# PCB.net
KiCad netlist of a schematic drawn in EasyEDA Pro
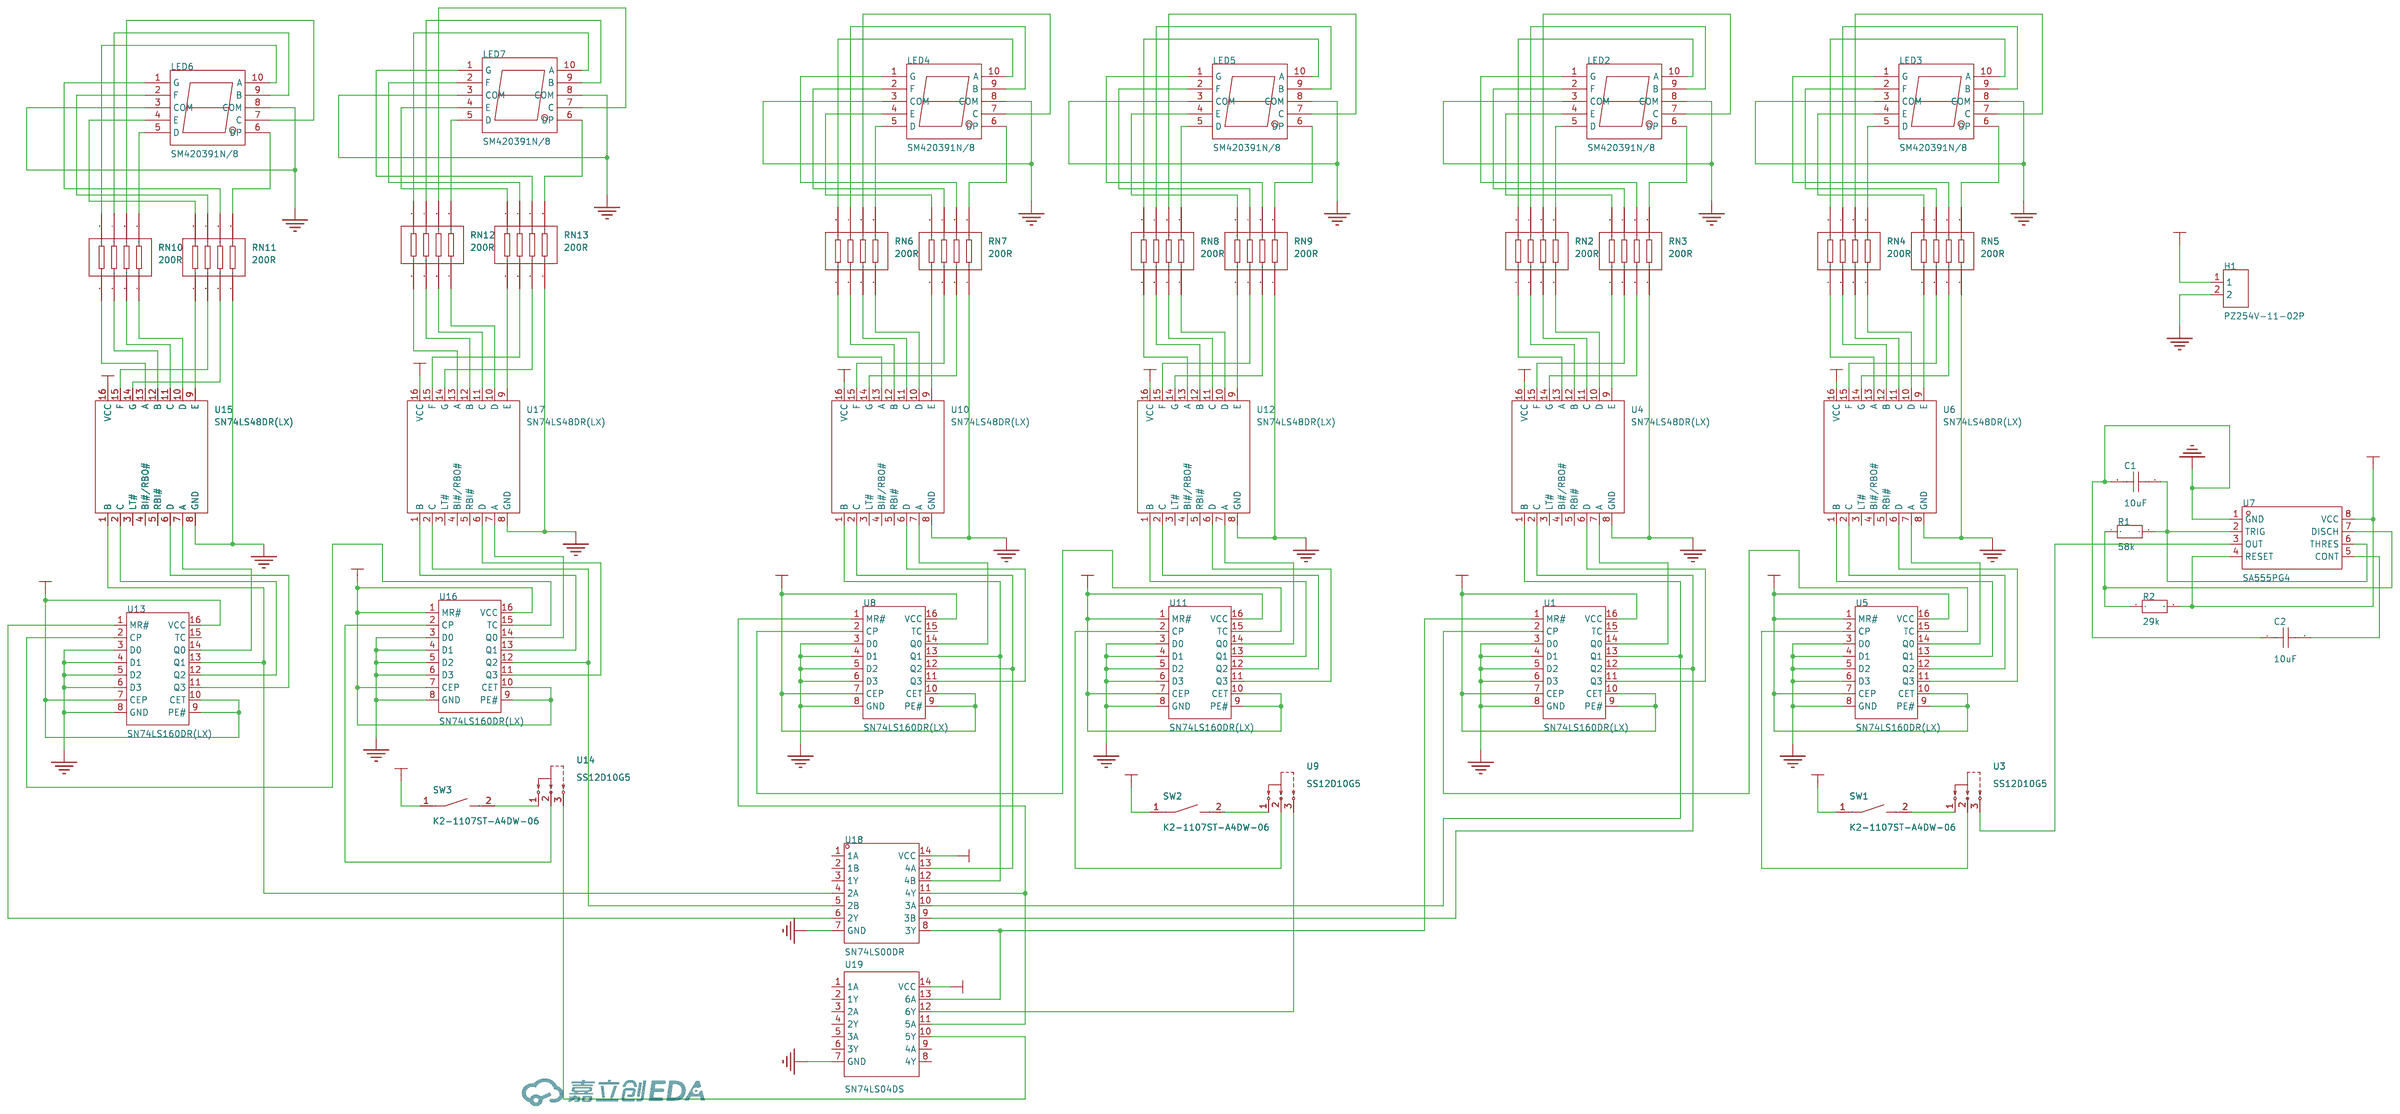
[diagram p0: schematic sheet]

(export (version "E")
  (design (tool "Eeschema 10.0.6"))
  (components
    (comp (ref "C1")
      (value "10uF")
      (footprint "easyedapro:C0603")
      (description "容值:100nF;精度:±10%;额定电压:50V;温度系数:X7R;")
      (fields
        (field (name "Manufacturer Part") "CGA0603X7R104K500JT")
        (field (name "Manufacturer") "HRE(芯声)")
      )
      (libsource (lib "easyedapro") (part "CGA0603X7R104K500JT"))
    )
    (comp (ref "C2")
      (value "10uF")
      (footprint "easyedapro:C0603")
      (description "容值:100nF;精度:±10%;额定电压:50V;温度系数:X7R;")
      (fields
        (field (name "Manufacturer Part") "CGA0603X7R104K500JT")
        (field (name "Manufacturer") "HRE(芯声)")
      )
      (libsource (lib "easyedapro") (part "CGA0603X7R104K500JT"))
    )
    (comp (ref "H1")
      (value "PZ254V-11-02P")
      (footprint "easyedapro:HDR-TH_2P-P2.54-V-M")
      (fields (field (name "Manufacturer") "XFCN(兴飞)"))
      (libsource (lib "easyedapro") (part "PZ254V-11-02P"))
    )
    (comp (ref "LED2")
      (value "SM420391N/8")
      (footprint "easyedapro:LED-SEG-TH_10P-L10.0-W13.0-P2.54-S7.62-TL")
      (description "数码管位数:1位;字符尺寸(英寸):0.39;发光颜色:红色;LED极性:共阴极;")
      (fields (field (name "Manufacturer") "ARKLED(方舟)"))
      (libsource (lib "easyedapro") (part "SM420391N/8"))
    )
    (comp (ref "LED3")
      (value "SM420391N/8")
      (footprint "easyedapro:LED-SEG-TH_10P-L10.0-W13.0-P2.54-S7.62-TL")
      (description "数码管位数:1位;字符尺寸(英寸):0.39;发光颜色:红色;LED极性:共阴极;")
      (fields (field (name "Manufacturer") "ARKLED(方舟)"))
      (libsource (lib "easyedapro") (part "SM420391N/8"))
    )
    (comp (ref "LED4")
      (value "SM420391N/8")
      (footprint "easyedapro:LED-SEG-TH_10P-L10.0-W13.0-P2.54-S7.62-TL")
      (description "数码管位数:1位;字符尺寸(英寸):0.39;发光颜色:红色;LED极性:共阴极;")
      (fields (field (name "Manufacturer") "ARKLED(方舟)"))
      (libsource (lib "easyedapro") (part "SM420391N/8"))
    )
    (comp (ref "LED5")
      (value "SM420391N/8")
      (footprint "easyedapro:LED-SEG-TH_10P-L10.0-W13.0-P2.54-S7.62-TL")
      (description "数码管位数:1位;字符尺寸(英寸):0.39;发光颜色:红色;LED极性:共阴极;")
      (fields (field (name "Manufacturer") "ARKLED(方舟)"))
      (libsource (lib "easyedapro") (part "SM420391N/8"))
    )
    (comp (ref "LED6")
      (value "SM420391N/8")
      (footprint "easyedapro:LED-SEG-TH_10P-L10.0-W13.0-P2.54-S7.62-TL")
      (description "数码管位数:1位;字符尺寸(英寸):0.39;发光颜色:红色;LED极性:共阴极;")
      (fields (field (name "Manufacturer") "ARKLED(方舟)"))
      (libsource (lib "easyedapro") (part "SM420391N/8"))
    )
    (comp (ref "LED7")
      (value "SM420391N/8")
      (footprint "easyedapro:LED-SEG-TH_10P-L10.0-W13.0-P2.54-S7.62-TL")
      (description "数码管位数:1位;字符尺寸(英寸):0.39;发光颜色:红色;LED极性:共阴极;")
      (fields (field (name "Manufacturer") "ARKLED(方舟)"))
      (libsource (lib "easyedapro") (part "SM420391N/8"))
    )
    (comp (ref "R1")
      (value "58k")
      (footprint "easyedapro:R2512")
      (description "电阻类型:采样电阻；合金电阻;阻值:5mΩ;精度:±1%;功率:3W;温度系数:±50ppm/°C;")
      (fields (field (name "Manufacturer Part") "JER2512F3R005") (field (name "Manufacturer") "JIERR(捷而瑞)"))
      (libsource (lib "easyedapro") (part "JER2512F3R005"))
    )
    (comp (ref "R2")
      (value "29k")
      (footprint "easyedapro:R2512")
      (description "电阻类型:采样电阻；合金电阻;阻值:5mΩ;精度:±1%;功率:3W;温度系数:±50ppm/°C;")
      (fields (field (name "Manufacturer Part") "JER2512F3R005") (field (name "Manufacturer") "JIERR(捷而瑞)"))
      (libsource (lib "easyedapro") (part "JER2512F3R005"))
    )
    (comp (ref "RN2")
      (value "200R")
      (footprint "easyedapro:RES-ARRAY-SMD_0603-8P-L3.2-W1.6-BL")
      (description "电阻器数:4;阻值:10kΩ;精度:±5%;单个元件功率:62.5mW;温度系数:±200ppm/°C;")
      (fields
        (field (name "Manufacturer Part") "4D03WGJ0103T5E")
        (field (name "Manufacturer") "UNI-ROYAL(厚声)")
      )
      (libsource (lib "easyedapro") (part "4D03WGJ0103T5E"))
    )
    (comp (ref "RN3")
      (value "200R")
      (footprint "easyedapro:RES-ARRAY-SMD_0603-8P-L3.2-W1.6-BL")
      (description "电阻器数:4;阻值:10kΩ;精度:±5%;单个元件功率:62.5mW;温度系数:±200ppm/°C;")
      (fields
        (field (name "Manufacturer Part") "4D03WGJ0103T5E")
        (field (name "Manufacturer") "UNI-ROYAL(厚声)")
      )
      (libsource (lib "easyedapro") (part "4D03WGJ0103T5E"))
    )
    (comp (ref "RN4")
      (value "200R")
      (footprint "easyedapro:RES-ARRAY-SMD_0603-8P-L3.2-W1.6-BL")
      (description "电阻器数:4;阻值:10kΩ;精度:±5%;单个元件功率:62.5mW;温度系数:±200ppm/°C;")
      (fields
        (field (name "Manufacturer Part") "4D03WGJ0103T5E")
        (field (name "Manufacturer") "UNI-ROYAL(厚声)")
      )
      (libsource (lib "easyedapro") (part "4D03WGJ0103T5E"))
    )
    (comp (ref "RN5")
      (value "200R")
      (footprint "easyedapro:RES-ARRAY-SMD_0603-8P-L3.2-W1.6-BL")
      (description "电阻器数:4;阻值:10kΩ;精度:±5%;单个元件功率:62.5mW;温度系数:±200ppm/°C;")
      (fields
        (field (name "Manufacturer Part") "4D03WGJ0103T5E")
        (field (name "Manufacturer") "UNI-ROYAL(厚声)")
      )
      (libsource (lib "easyedapro") (part "4D03WGJ0103T5E"))
    )
    (comp (ref "RN6")
      (value "200R")
      (footprint "easyedapro:RES-ARRAY-SMD_0603-8P-L3.2-W1.6-BL")
      (description "电阻器数:4;阻值:10kΩ;精度:±5%;单个元件功率:62.5mW;温度系数:±200ppm/°C;")
      (fields
        (field (name "Manufacturer Part") "4D03WGJ0103T5E")
        (field (name "Manufacturer") "UNI-ROYAL(厚声)")
      )
      (libsource (lib "easyedapro") (part "4D03WGJ0103T5E"))
    )
    (comp (ref "RN7")
      (value "200R")
      (footprint "easyedapro:RES-ARRAY-SMD_0603-8P-L3.2-W1.6-BL")
      (description "电阻器数:4;阻值:10kΩ;精度:±5%;单个元件功率:62.5mW;温度系数:±200ppm/°C;")
      (fields
        (field (name "Manufacturer Part") "4D03WGJ0103T5E")
        (field (name "Manufacturer") "UNI-ROYAL(厚声)")
      )
      (libsource (lib "easyedapro") (part "4D03WGJ0103T5E"))
    )
    (comp (ref "RN8")
      (value "200R")
      (footprint "easyedapro:RES-ARRAY-SMD_0603-8P-L3.2-W1.6-BL")
      (description "电阻器数:4;阻值:10kΩ;精度:±5%;单个元件功率:62.5mW;温度系数:±200ppm/°C;")
      (fields
        (field (name "Manufacturer Part") "4D03WGJ0103T5E")
        (field (name "Manufacturer") "UNI-ROYAL(厚声)")
      )
      (libsource (lib "easyedapro") (part "4D03WGJ0103T5E"))
    )
    (comp (ref "RN9")
      (value "200R")
      (footprint "easyedapro:RES-ARRAY-SMD_0603-8P-L3.2-W1.6-BL")
      (description "电阻器数:4;阻值:10kΩ;精度:±5%;单个元件功率:62.5mW;温度系数:±200ppm/°C;")
      (fields
        (field (name "Manufacturer Part") "4D03WGJ0103T5E")
        (field (name "Manufacturer") "UNI-ROYAL(厚声)")
      )
      (libsource (lib "easyedapro") (part "4D03WGJ0103T5E"))
    )
    (comp (ref "RN10")
      (value "200R")
      (footprint "easyedapro:RES-ARRAY-SMD_0603-8P-L3.2-W1.6-BL")
      (description "电阻器数:4;阻值:10kΩ;精度:±5%;单个元件功率:62.5mW;温度系数:±200ppm/°C;")
      (fields
        (field (name "Manufacturer Part") "4D03WGJ0103T5E")
        (field (name "Manufacturer") "UNI-ROYAL(厚声)")
      )
      (libsource (lib "easyedapro") (part "4D03WGJ0103T5E"))
    )
    (comp (ref "RN11")
      (value "200R")
      (footprint "easyedapro:RES-ARRAY-SMD_0603-8P-L3.2-W1.6-BL")
      (description "电阻器数:4;阻值:10kΩ;精度:±5%;单个元件功率:62.5mW;温度系数:±200ppm/°C;")
      (fields
        (field (name "Manufacturer Part") "4D03WGJ0103T5E")
        (field (name "Manufacturer") "UNI-ROYAL(厚声)")
      )
      (libsource (lib "easyedapro") (part "4D03WGJ0103T5E"))
    )
    (comp (ref "RN12")
      (value "200R")
      (footprint "easyedapro:RES-ARRAY-SMD_0603-8P-L3.2-W1.6-BL")
      (description "电阻器数:4;阻值:10kΩ;精度:±5%;单个元件功率:62.5mW;温度系数:±200ppm/°C;")
      (fields
        (field (name "Manufacturer Part") "4D03WGJ0103T5E")
        (field (name "Manufacturer") "UNI-ROYAL(厚声)")
      )
      (libsource (lib "easyedapro") (part "4D03WGJ0103T5E"))
    )
    (comp (ref "RN13")
      (value "200R")
      (footprint "easyedapro:RES-ARRAY-SMD_0603-8P-L3.2-W1.6-BL")
      (description "电阻器数:4;阻值:10kΩ;精度:±5%;单个元件功率:62.5mW;温度系数:±200ppm/°C;")
      (fields
        (field (name "Manufacturer Part") "4D03WGJ0103T5E")
        (field (name "Manufacturer") "UNI-ROYAL(厚声)")
      )
      (libsource (lib "easyedapro") (part "4D03WGJ0103T5E"))
    )
    (comp (ref "SW1")
      (value "K2-1107ST-A4DW-06")
      (footprint "easyedapro:KEY-SMD_L6.2-W3.6-LS8.0_K2-1107ST-A4SW-06")
      (fields (field (name "Manufacturer") "韩国韩荣"))
      (libsource (lib "easyedapro") (part "K2-1107ST-A4SW-06"))
    )
    (comp (ref "SW2")
      (value "K2-1107ST-A4DW-06")
      (footprint "easyedapro:KEY-SMD_L6.2-W3.6-LS8.0_K2-1107ST-A4SW-06")
      (fields (field (name "Manufacturer") "韩国韩荣"))
      (libsource (lib "easyedapro") (part "K2-1107ST-A4SW-06"))
    )
    (comp (ref "SW3")
      (value "K2-1107ST-A4DW-06")
      (footprint "easyedapro:KEY-SMD_L6.2-W3.6-LS8.0_K2-1107ST-A4SW-06")
      (fields (field (name "Manufacturer") "韩国韩荣"))
      (libsource (lib "easyedapro") (part "K2-1107ST-A4SW-06"))
    )
    (comp (ref "U1")
      (value "SN74LS160DR(LX)")
      (footprint "easyedapro:DIP-16_L19.4-W6.4-P2.54-S7.6-BL")
      (description "工作电压:2V~6V;触发沿:上升沿;计数速率:35MHz;")
      (fields (field (name "Manufacturer") "LX(灵星芯微)"))
      (libsource (lib "easyedapro") (part "SN74LS160N(LX)"))
    )
    (comp (ref "U3")
      (value "SS12D10G5")
      (footprint "easyedapro:SW-TH_SHOU-HAN_SS12D10G4")
      (description "电路结构:单刀双掷;安装方式:直插;额定电流:2A;额定电压:125V;工作寿命:3千次;")
      (fields (field (name "Manufacturer") "SHOU HAN(首韩)"))
      (libsource (lib "easyedapro") (part "SS12D10G5"))
    )
    (comp (ref "U4")
      (value "SN74LS48DR(LX)")
      (footprint "easyedapro:DIP-16_L19.2-W6.6-P2.54-LS8.8-BL")
      (description "接口类型:-;工作电压:2V~6V;时钟频率(fc):-;位驱动电流:-;段驱动电流:-;")
      (fields (field (name "Manufacturer") "LX(灵星芯微)"))
      (libsource (lib "easyedapro") (part "SN74LS48N(XBLW)"))
    )
    (comp (ref "U5")
      (value "SN74LS160DR(LX)")
      (footprint "easyedapro:DIP-16_L19.4-W6.4-P2.54-S7.6-BL")
      (description "工作电压:2V~6V;触发沿:上升沿;计数速率:35MHz;")
      (fields (field (name "Manufacturer") "LX(灵星芯微)"))
      (libsource (lib "easyedapro") (part "SN74LS160N(LX)"))
    )
    (comp (ref "U6")
      (value "SN74LS48DR(LX)")
      (footprint "easyedapro:DIP-16_L19.2-W6.6-P2.54-LS8.8-BL")
      (description "接口类型:-;工作电压:2V~6V;时钟频率(fc):-;位驱动电流:-;段驱动电流:-;")
      (fields (field (name "Manufacturer") "LX(灵星芯微)"))
      (libsource (lib "easyedapro") (part "SN74LS48N(XBLW)"))
    )
    (comp (ref "U7")
      (value "SA555PG4")
      (footprint "easyedapro:PDIP-8_L9.6-W6.4-P2.54-LS7.6-BL")
      (fields (field (name "Manufacturer") "TI(德州仪器)"))
      (libsource (lib "easyedapro") (part "SA555PG4"))
    )
    (comp (ref "U8")
      (value "SN74LS160DR(LX)")
      (footprint "easyedapro:DIP-16_L19.4-W6.4-P2.54-S7.6-BL")
      (description "工作电压:2V~6V;触发沿:上升沿;计数速率:35MHz;")
      (fields (field (name "Manufacturer") "LX(灵星芯微)"))
      (libsource (lib "easyedapro") (part "SN74LS160N(LX)"))
    )
    (comp (ref "U9")
      (value "SS12D10G5")
      (footprint "easyedapro:SW-TH_SHOU-HAN_SS12D10G4")
      (description "电路结构:单刀双掷;安装方式:直插;额定电流:2A;额定电压:125V;工作寿命:3千次;")
      (fields (field (name "Manufacturer") "SHOU HAN(首韩)"))
      (libsource (lib "easyedapro") (part "SS12D10G5"))
    )
    (comp (ref "U10")
      (value "SN74LS48DR(LX)")
      (footprint "easyedapro:DIP-16_L19.2-W6.6-P2.54-LS8.8-BL")
      (description "接口类型:-;工作电压:2V~6V;时钟频率(fc):-;位驱动电流:-;段驱动电流:-;")
      (fields (field (name "Manufacturer") "LX(灵星芯微)"))
      (libsource (lib "easyedapro") (part "SN74LS48N(XBLW)"))
    )
    (comp (ref "U11")
      (value "SN74LS160DR(LX)")
      (footprint "easyedapro:DIP-16_L19.4-W6.4-P2.54-S7.6-BL")
      (description "工作电压:2V~6V;触发沿:上升沿;计数速率:35MHz;")
      (fields (field (name "Manufacturer") "LX(灵星芯微)"))
      (libsource (lib "easyedapro") (part "SN74LS160N(LX)"))
    )
    (comp (ref "U12")
      (value "SN74LS48DR(LX)")
      (footprint "easyedapro:DIP-16_L19.2-W6.6-P2.54-LS8.8-BL")
      (description "接口类型:-;工作电压:2V~6V;时钟频率(fc):-;位驱动电流:-;段驱动电流:-;")
      (fields (field (name "Manufacturer") "LX(灵星芯微)"))
      (libsource (lib "easyedapro") (part "SN74LS48N(XBLW)"))
    )
    (comp (ref "U13")
      (value "SN74LS160DR(LX)")
      (footprint "easyedapro:DIP-16_L19.4-W6.4-P2.54-S7.6-BL")
      (description "工作电压:2V~6V;触发沿:上升沿;计数速率:35MHz;")
      (fields (field (name "Manufacturer") "LX(灵星芯微)"))
      (libsource (lib "easyedapro") (part "SN74LS160N(LX)"))
    )
    (comp (ref "U14")
      (value "SS12D10G5")
      (footprint "easyedapro:SW-TH_SHOU-HAN_SS12D10G4")
      (description "电路结构:单刀双掷;安装方式:直插;额定电流:2A;额定电压:125V;工作寿命:3千次;")
      (fields (field (name "Manufacturer") "SHOU HAN(首韩)"))
      (libsource (lib "easyedapro") (part "SS12D10G5"))
    )
    (comp (ref "U15")
      (value "SN74LS48DR(LX)")
      (footprint "easyedapro:DIP-16_L19.2-W6.6-P2.54-LS8.8-BL")
      (description "接口类型:-;工作电压:2V~6V;时钟频率(fc):-;位驱动电流:-;段驱动电流:-;")
      (fields (field (name "Manufacturer") "LX(灵星芯微)"))
      (libsource (lib "easyedapro") (part "SN74LS48N(XBLW)"))
    )
    (comp (ref "U16")
      (value "SN74LS160DR(LX)")
      (footprint "easyedapro:DIP-16_L19.4-W6.4-P2.54-S7.6-BL")
      (description "工作电压:2V~6V;触发沿:上升沿;计数速率:35MHz;")
      (fields (field (name "Manufacturer") "LX(灵星芯微)"))
      (libsource (lib "easyedapro") (part "SN74LS160N(LX)"))
    )
    (comp (ref "U17")
      (value "SN74LS48DR(LX)")
      (footprint "easyedapro:DIP-16_L19.2-W6.6-P2.54-LS8.8-BL")
      (description "接口类型:-;工作电压:2V~6V;时钟频率(fc):-;位驱动电流:-;段驱动电流:-;")
      (fields (field (name "Manufacturer") "LX(灵星芯微)"))
      (libsource (lib "easyedapro") (part "SN74LS48N(XBLW)"))
    )
    (comp (ref "U18")
      (value "SN74LS00DR")
      (footprint "easyedapro:SOIC-14_L8.7-W3.9-P1.27-LS6.0-BL")
      (description "逻辑类型:与非门;通道数:4;工作电压:4.75V~5.25V;传播延迟(tpd):15ns@5V,15pF;")
      (fields (field (name "Manufacturer") "TI(德州仪器)"))
      (libsource (lib "easyedapro") (part "SN74LS00DR"))
    )
    (comp (ref "U19")
      (value "SN74LS04DS")
      (footprint "easyedapro:SOP-14_L8.6-W3.9-P1.27-LS6.0-BL")
      (description "输入类型:-;工作电压:2V~6V;静态电流(Iq):2uA;通道数:6;传播延迟(tpd):14ns@6V;")
      (fields (field (name "Manufacturer") "GMIC(绿微)"))
      (libsource (lib "easyedapro") (part "SN74LS04DS"))
    )
  )
  (nets
    (net (code "1") (name "+5V") (class "Default")
      (node (ref "H1") (pin "1") (pinfunction "1_1") (pintype "unspecified"))
      (node (ref "R2") (pin "2") (pinfunction "2_2") (pintype "unspecified"))
      (node (ref "SW1") (pin "1") (pinfunction "1_1") (pintype "unspecified"))
      (node (ref "SW2") (pin "1") (pinfunction "1_1") (pintype "unspecified"))
      (node (ref "SW3") (pin "1") (pinfunction "1_1") (pintype "unspecified"))
      (node (ref "U1") (pin "10") (pinfunction "CET_10") (pintype "unspecified"))
      (node (ref "U1") (pin "16") (pinfunction "VCC_16") (pintype "unspecified"))
      (node (ref "U1") (pin "7") (pinfunction "CEP_7") (pintype "unspecified"))
      (node (ref "U1") (pin "9") (pinfunction "PE#_9") (pintype "unspecified"))
      (node (ref "U10") (pin "16") (pinfunction "VCC_16") (pintype "unspecified"))
      (node (ref "U11") (pin "1") (pinfunction "MR#_1") (pintype "unspecified"))
      (node (ref "U11") (pin "10") (pinfunction "CET_10") (pintype "unspecified"))
      (node (ref "U11") (pin "16") (pinfunction "VCC_16") (pintype "unspecified"))
      (node (ref "U11") (pin "7") (pinfunction "CEP_7") (pintype "unspecified"))
      (node (ref "U11") (pin "9") (pinfunction "PE#_9") (pintype "unspecified"))
      (node (ref "U12") (pin "16") (pinfunction "VCC_16") (pintype "unspecified"))
      (node (ref "U13") (pin "10") (pinfunction "CET_10") (pintype "unspecified"))
      (node (ref "U13") (pin "16") (pinfunction "VCC_16") (pintype "unspecified"))
      (node (ref "U13") (pin "7") (pinfunction "CEP_7") (pintype "unspecified"))
      (node (ref "U13") (pin "9") (pinfunction "PE#_9") (pintype "unspecified"))
      (node (ref "U15") (pin "16") (pinfunction "VCC_16") (pintype "unspecified"))
      (node (ref "U16") (pin "1") (pinfunction "MR#_1") (pintype "unspecified"))
      (node (ref "U16") (pin "10") (pinfunction "CET_10") (pintype "unspecified"))
      (node (ref "U16") (pin "16") (pinfunction "VCC_16") (pintype "unspecified"))
      (node (ref "U16") (pin "7") (pinfunction "CEP_7") (pintype "unspecified"))
      (node (ref "U16") (pin "9") (pinfunction "PE#_9") (pintype "unspecified"))
      (node (ref "U17") (pin "16") (pinfunction "VCC_16") (pintype "unspecified"))
      (node (ref "U18") (pin "14") (pinfunction "VCC_14") (pintype "unspecified"))
      (node (ref "U19") (pin "14") (pinfunction "VCC_14") (pintype "unspecified"))
      (node (ref "U4") (pin "16") (pinfunction "VCC_16") (pintype "unspecified"))
      (node (ref "U5") (pin "1") (pinfunction "MR#_1") (pintype "unspecified"))
      (node (ref "U5") (pin "10") (pinfunction "CET_10") (pintype "unspecified"))
      (node (ref "U5") (pin "16") (pinfunction "VCC_16") (pintype "unspecified"))
      (node (ref "U5") (pin "7") (pinfunction "CEP_7") (pintype "unspecified"))
      (node (ref "U5") (pin "9") (pinfunction "PE#_9") (pintype "unspecified"))
      (node (ref "U6") (pin "16") (pinfunction "VCC_16") (pintype "unspecified"))
      (node (ref "U7") (pin "4") (pinfunction "RESET_4") (pintype "unspecified"))
      (node (ref "U7") (pin "8") (pinfunction "VCC_8") (pintype "unspecified"))
      (node (ref "U8") (pin "10") (pinfunction "CET_10") (pintype "unspecified"))
      (node (ref "U8") (pin "16") (pinfunction "VCC_16") (pintype "unspecified"))
      (node (ref "U8") (pin "7") (pinfunction "CEP_7") (pintype "unspecified"))
      (node (ref "U8") (pin "9") (pinfunction "PE#_9") (pintype "unspecified"))
    )
    (net (code "2") (name "GND") (class "Default")
      (node (ref "C1") (pin "2") (pinfunction "2_2") (pintype "unspecified"))
      (node (ref "C2") (pin "1") (pinfunction "1_1") (pintype "unspecified"))
      (node (ref "H1") (pin "2") (pinfunction "2_2") (pintype "unspecified"))
      (node (ref "LED2") (pin "3") (pinfunction "COM_3") (pintype "unspecified"))
      (node (ref "LED2") (pin "8") (pinfunction "COM_8") (pintype "unspecified"))
      (node (ref "LED3") (pin "3") (pinfunction "COM_3") (pintype "unspecified"))
      (node (ref "LED3") (pin "8") (pinfunction "COM_8") (pintype "unspecified"))
      (node (ref "LED4") (pin "3") (pinfunction "COM_3") (pintype "unspecified"))
      (node (ref "LED4") (pin "8") (pinfunction "COM_8") (pintype "unspecified"))
      (node (ref "LED5") (pin "3") (pinfunction "COM_3") (pintype "unspecified"))
      (node (ref "LED5") (pin "8") (pinfunction "COM_8") (pintype "unspecified"))
      (node (ref "LED6") (pin "3") (pinfunction "COM_3") (pintype "unspecified"))
      (node (ref "LED6") (pin "8") (pinfunction "COM_8") (pintype "unspecified"))
      (node (ref "LED7") (pin "3") (pinfunction "COM_3") (pintype "unspecified"))
      (node (ref "LED7") (pin "8") (pinfunction "COM_8") (pintype "unspecified"))
      (node (ref "RN11") (pin "4") (pinfunction "4_4") (pintype "input"))
      (node (ref "RN13") (pin "4") (pinfunction "4_4") (pintype "input"))
      (node (ref "RN3") (pin "4") (pinfunction "4_4") (pintype "input"))
      (node (ref "RN5") (pin "4") (pinfunction "4_4") (pintype "input"))
      (node (ref "RN7") (pin "4") (pinfunction "4_4") (pintype "input"))
      (node (ref "RN9") (pin "4") (pinfunction "4_4") (pintype "input"))
      (node (ref "U1") (pin "3") (pinfunction "D0_3") (pintype "unspecified"))
      (node (ref "U1") (pin "4") (pinfunction "D1_4") (pintype "unspecified"))
      (node (ref "U1") (pin "5") (pinfunction "D2_5") (pintype "unspecified"))
      (node (ref "U1") (pin "6") (pinfunction "D3_6") (pintype "unspecified"))
      (node (ref "U1") (pin "8") (pinfunction "GND_8") (pintype "unspecified"))
      (node (ref "U10") (pin "8") (pinfunction "GND_8") (pintype "unspecified"))
      (node (ref "U11") (pin "3") (pinfunction "D0_3") (pintype "unspecified"))
      (node (ref "U11") (pin "4") (pinfunction "D1_4") (pintype "unspecified"))
      (node (ref "U11") (pin "5") (pinfunction "D2_5") (pintype "unspecified"))
      (node (ref "U11") (pin "6") (pinfunction "D3_6") (pintype "unspecified"))
      (node (ref "U11") (pin "8") (pinfunction "GND_8") (pintype "unspecified"))
      (node (ref "U12") (pin "8") (pinfunction "GND_8") (pintype "unspecified"))
      (node (ref "U13") (pin "3") (pinfunction "D0_3") (pintype "unspecified"))
      (node (ref "U13") (pin "4") (pinfunction "D1_4") (pintype "unspecified"))
      (node (ref "U13") (pin "5") (pinfunction "D2_5") (pintype "unspecified"))
      (node (ref "U13") (pin "6") (pinfunction "D3_6") (pintype "unspecified"))
      (node (ref "U13") (pin "8") (pinfunction "GND_8") (pintype "unspecified"))
      (node (ref "U15") (pin "8") (pinfunction "GND_8") (pintype "unspecified"))
      (node (ref "U16") (pin "3") (pinfunction "D0_3") (pintype "unspecified"))
      (node (ref "U16") (pin "4") (pinfunction "D1_4") (pintype "unspecified"))
      (node (ref "U16") (pin "5") (pinfunction "D2_5") (pintype "unspecified"))
      (node (ref "U16") (pin "6") (pinfunction "D3_6") (pintype "unspecified"))
      (node (ref "U16") (pin "8") (pinfunction "GND_8") (pintype "unspecified"))
      (node (ref "U17") (pin "8") (pinfunction "GND_8") (pintype "unspecified"))
      (node (ref "U18") (pin "7") (pinfunction "GND_7") (pintype "unspecified"))
      (node (ref "U19") (pin "7") (pinfunction "GND_7") (pintype "unspecified"))
      (node (ref "U4") (pin "8") (pinfunction "GND_8") (pintype "unspecified"))
      (node (ref "U5") (pin "3") (pinfunction "D0_3") (pintype "unspecified"))
      (node (ref "U5") (pin "4") (pinfunction "D1_4") (pintype "unspecified"))
      (node (ref "U5") (pin "5") (pinfunction "D2_5") (pintype "unspecified"))
      (node (ref "U5") (pin "6") (pinfunction "D3_6") (pintype "unspecified"))
      (node (ref "U5") (pin "8") (pinfunction "GND_8") (pintype "unspecified"))
      (node (ref "U6") (pin "8") (pinfunction "GND_8") (pintype "unspecified"))
      (node (ref "U7") (pin "1") (pinfunction "GND_1") (pintype "unspecified"))
      (node (ref "U8") (pin "3") (pinfunction "D0_3") (pintype "unspecified"))
      (node (ref "U8") (pin "4") (pinfunction "D1_4") (pintype "unspecified"))
      (node (ref "U8") (pin "5") (pinfunction "D2_5") (pintype "unspecified"))
      (node (ref "U8") (pin "6") (pinfunction "D3_6") (pintype "unspecified"))
      (node (ref "U8") (pin "8") (pinfunction "GND_8") (pintype "unspecified"))
    )
    (net (code "3") (name "Net-(LED2-A)") (class "Default")
      (node (ref "LED2") (pin "10") (pinfunction "A_10") (pintype "unspecified"))
      (node (ref "RN2") (pin "8") (pinfunction "8_8") (pintype "input"))
    )
    (net (code "4") (name "Net-(LED2-B)") (class "Default")
      (node (ref "LED2") (pin "9") (pinfunction "B_9") (pintype "unspecified"))
      (node (ref "RN2") (pin "7") (pinfunction "7_7") (pintype "input"))
    )
    (net (code "5") (name "Net-(LED2-C)") (class "Default")
      (node (ref "LED2") (pin "7") (pinfunction "C_7") (pintype "unspecified"))
      (node (ref "RN2") (pin "6") (pinfunction "6_6") (pintype "input"))
    )
    (net (code "6") (name "Net-(LED2-D)") (class "Default")
      (node (ref "LED2") (pin "5") (pinfunction "D_5") (pintype "unspecified"))
      (node (ref "RN2") (pin "5") (pinfunction "5_5") (pintype "input"))
    )
    (net (code "7") (name "Net-(LED2-DP)") (class "Default")
      (node (ref "LED2") (pin "6") (pinfunction "DP_6") (pintype "unspecified"))
      (node (ref "RN3") (pin "5") (pinfunction "5_5") (pintype "input"))
    )
    (net (code "8") (name "Net-(LED2-E)") (class "Default")
      (node (ref "LED2") (pin "4") (pinfunction "E_4") (pintype "unspecified"))
      (node (ref "RN3") (pin "8") (pinfunction "8_8") (pintype "input"))
    )
    (net (code "9") (name "Net-(LED2-F)") (class "Default")
      (node (ref "LED2") (pin "2") (pinfunction "F_2") (pintype "unspecified"))
      (node (ref "RN3") (pin "7") (pinfunction "7_7") (pintype "input"))
    )
    (net (code "10") (name "Net-(LED2-G)") (class "Default")
      (node (ref "LED2") (pin "1") (pinfunction "G_1") (pintype "unspecified"))
      (node (ref "RN3") (pin "6") (pinfunction "6_6") (pintype "input"))
    )
    (net (code "11") (name "Net-(LED3-A)") (class "Default")
      (node (ref "LED3") (pin "10") (pinfunction "A_10") (pintype "unspecified"))
      (node (ref "RN4") (pin "8") (pinfunction "8_8") (pintype "input"))
    )
    (net (code "12") (name "Net-(LED3-B)") (class "Default")
      (node (ref "LED3") (pin "9") (pinfunction "B_9") (pintype "unspecified"))
      (node (ref "RN4") (pin "7") (pinfunction "7_7") (pintype "input"))
    )
    (net (code "13") (name "Net-(LED3-C)") (class "Default")
      (node (ref "LED3") (pin "7") (pinfunction "C_7") (pintype "unspecified"))
      (node (ref "RN4") (pin "6") (pinfunction "6_6") (pintype "input"))
    )
    (net (code "14") (name "Net-(LED3-D)") (class "Default")
      (node (ref "LED3") (pin "5") (pinfunction "D_5") (pintype "unspecified"))
      (node (ref "RN4") (pin "5") (pinfunction "5_5") (pintype "input"))
    )
    (net (code "15") (name "Net-(LED3-DP)") (class "Default")
      (node (ref "LED3") (pin "6") (pinfunction "DP_6") (pintype "unspecified"))
      (node (ref "RN5") (pin "5") (pinfunction "5_5") (pintype "input"))
    )
    (net (code "16") (name "Net-(LED3-E)") (class "Default")
      (node (ref "LED3") (pin "4") (pinfunction "E_4") (pintype "unspecified"))
      (node (ref "RN5") (pin "8") (pinfunction "8_8") (pintype "input"))
    )
    (net (code "17") (name "Net-(LED3-F)") (class "Default")
      (node (ref "LED3") (pin "2") (pinfunction "F_2") (pintype "unspecified"))
      (node (ref "RN5") (pin "7") (pinfunction "7_7") (pintype "input"))
    )
    (net (code "18") (name "Net-(LED3-G)") (class "Default")
      (node (ref "LED3") (pin "1") (pinfunction "G_1") (pintype "unspecified"))
      (node (ref "RN5") (pin "6") (pinfunction "6_6") (pintype "input"))
    )
    (net (code "19") (name "Net-(LED4-A)") (class "Default")
      (node (ref "LED4") (pin "10") (pinfunction "A_10") (pintype "unspecified"))
      (node (ref "RN6") (pin "8") (pinfunction "8_8") (pintype "input"))
    )
    (net (code "20") (name "Net-(LED4-B)") (class "Default")
      (node (ref "LED4") (pin "9") (pinfunction "B_9") (pintype "unspecified"))
      (node (ref "RN6") (pin "7") (pinfunction "7_7") (pintype "input"))
    )
    (net (code "21") (name "Net-(LED4-C)") (class "Default")
      (node (ref "LED4") (pin "7") (pinfunction "C_7") (pintype "unspecified"))
      (node (ref "RN6") (pin "6") (pinfunction "6_6") (pintype "input"))
    )
    (net (code "22") (name "Net-(LED4-D)") (class "Default")
      (node (ref "LED4") (pin "5") (pinfunction "D_5") (pintype "unspecified"))
      (node (ref "RN6") (pin "5") (pinfunction "5_5") (pintype "input"))
    )
    (net (code "23") (name "Net-(LED4-DP)") (class "Default")
      (node (ref "LED4") (pin "6") (pinfunction "DP_6") (pintype "unspecified"))
      (node (ref "RN7") (pin "5") (pinfunction "5_5") (pintype "input"))
    )
    (net (code "24") (name "Net-(LED4-E)") (class "Default")
      (node (ref "LED4") (pin "4") (pinfunction "E_4") (pintype "unspecified"))
      (node (ref "RN7") (pin "8") (pinfunction "8_8") (pintype "input"))
    )
    (net (code "25") (name "Net-(LED4-F)") (class "Default")
      (node (ref "LED4") (pin "2") (pinfunction "F_2") (pintype "unspecified"))
      (node (ref "RN7") (pin "7") (pinfunction "7_7") (pintype "input"))
    )
    (net (code "26") (name "Net-(LED4-G)") (class "Default")
      (node (ref "LED4") (pin "1") (pinfunction "G_1") (pintype "unspecified"))
      (node (ref "RN7") (pin "6") (pinfunction "6_6") (pintype "input"))
    )
    (net (code "27") (name "Net-(LED5-A)") (class "Default")
      (node (ref "LED5") (pin "10") (pinfunction "A_10") (pintype "unspecified"))
      (node (ref "RN8") (pin "8") (pinfunction "8_8") (pintype "input"))
    )
    (net (code "28") (name "Net-(LED5-B)") (class "Default")
      (node (ref "LED5") (pin "9") (pinfunction "B_9") (pintype "unspecified"))
      (node (ref "RN8") (pin "7") (pinfunction "7_7") (pintype "input"))
    )
    (net (code "29") (name "Net-(LED5-C)") (class "Default")
      (node (ref "LED5") (pin "7") (pinfunction "C_7") (pintype "unspecified"))
      (node (ref "RN8") (pin "6") (pinfunction "6_6") (pintype "input"))
    )
    (net (code "30") (name "Net-(LED5-D)") (class "Default")
      (node (ref "LED5") (pin "5") (pinfunction "D_5") (pintype "unspecified"))
      (node (ref "RN8") (pin "5") (pinfunction "5_5") (pintype "input"))
    )
    (net (code "31") (name "Net-(LED5-DP)") (class "Default")
      (node (ref "LED5") (pin "6") (pinfunction "DP_6") (pintype "unspecified"))
      (node (ref "RN9") (pin "5") (pinfunction "5_5") (pintype "input"))
    )
    (net (code "32") (name "Net-(LED5-E)") (class "Default")
      (node (ref "LED5") (pin "4") (pinfunction "E_4") (pintype "unspecified"))
      (node (ref "RN9") (pin "8") (pinfunction "8_8") (pintype "input"))
    )
    (net (code "33") (name "Net-(LED5-F)") (class "Default")
      (node (ref "LED5") (pin "2") (pinfunction "F_2") (pintype "unspecified"))
      (node (ref "RN9") (pin "7") (pinfunction "7_7") (pintype "input"))
    )
    (net (code "34") (name "Net-(LED5-G)") (class "Default")
      (node (ref "LED5") (pin "1") (pinfunction "G_1") (pintype "unspecified"))
      (node (ref "RN9") (pin "6") (pinfunction "6_6") (pintype "input"))
    )
    (net (code "35") (name "Net-(LED6-A)") (class "Default")
      (node (ref "LED6") (pin "10") (pinfunction "A_10") (pintype "unspecified"))
      (node (ref "RN10") (pin "8") (pinfunction "8_8") (pintype "input"))
    )
    (net (code "36") (name "Net-(LED6-B)") (class "Default")
      (node (ref "LED6") (pin "9") (pinfunction "B_9") (pintype "unspecified"))
      (node (ref "RN10") (pin "7") (pinfunction "7_7") (pintype "input"))
    )
    (net (code "37") (name "Net-(LED6-C)") (class "Default")
      (node (ref "LED6") (pin "7") (pinfunction "C_7") (pintype "unspecified"))
      (node (ref "RN10") (pin "6") (pinfunction "6_6") (pintype "input"))
    )
    (net (code "38") (name "Net-(LED6-D)") (class "Default")
      (node (ref "LED6") (pin "5") (pinfunction "D_5") (pintype "unspecified"))
      (node (ref "RN10") (pin "5") (pinfunction "5_5") (pintype "input"))
    )
    (net (code "39") (name "Net-(LED6-DP)") (class "Default")
      (node (ref "LED6") (pin "6") (pinfunction "DP_6") (pintype "unspecified"))
      (node (ref "RN11") (pin "5") (pinfunction "5_5") (pintype "input"))
    )
    (net (code "40") (name "Net-(LED6-E)") (class "Default")
      (node (ref "LED6") (pin "4") (pinfunction "E_4") (pintype "unspecified"))
      (node (ref "RN11") (pin "8") (pinfunction "8_8") (pintype "input"))
    )
    (net (code "41") (name "Net-(LED6-F)") (class "Default")
      (node (ref "LED6") (pin "2") (pinfunction "F_2") (pintype "unspecified"))
      (node (ref "RN11") (pin "7") (pinfunction "7_7") (pintype "input"))
    )
    (net (code "42") (name "Net-(LED6-G)") (class "Default")
      (node (ref "LED6") (pin "1") (pinfunction "G_1") (pintype "unspecified"))
      (node (ref "RN11") (pin "6") (pinfunction "6_6") (pintype "input"))
    )
    (net (code "43") (name "Net-(LED7-A)") (class "Default")
      (node (ref "LED7") (pin "10") (pinfunction "A_10") (pintype "unspecified"))
      (node (ref "RN12") (pin "8") (pinfunction "8_8") (pintype "input"))
    )
    (net (code "44") (name "Net-(LED7-B)") (class "Default")
      (node (ref "LED7") (pin "9") (pinfunction "B_9") (pintype "unspecified"))
      (node (ref "RN12") (pin "7") (pinfunction "7_7") (pintype "input"))
    )
    (net (code "45") (name "Net-(LED7-C)") (class "Default")
      (node (ref "LED7") (pin "7") (pinfunction "C_7") (pintype "unspecified"))
      (node (ref "RN12") (pin "6") (pinfunction "6_6") (pintype "input"))
    )
    (net (code "46") (name "Net-(LED7-D)") (class "Default")
      (node (ref "LED7") (pin "5") (pinfunction "D_5") (pintype "unspecified"))
      (node (ref "RN12") (pin "5") (pinfunction "5_5") (pintype "input"))
    )
    (net (code "47") (name "Net-(LED7-DP)") (class "Default")
      (node (ref "LED7") (pin "6") (pinfunction "DP_6") (pintype "unspecified"))
      (node (ref "RN13") (pin "5") (pinfunction "5_5") (pintype "input"))
    )
    (net (code "48") (name "Net-(LED7-E)") (class "Default")
      (node (ref "LED7") (pin "4") (pinfunction "E_4") (pintype "unspecified"))
      (node (ref "RN13") (pin "8") (pinfunction "8_8") (pintype "input"))
    )
    (net (code "49") (name "Net-(LED7-F)") (class "Default")
      (node (ref "LED7") (pin "2") (pinfunction "F_2") (pintype "unspecified"))
      (node (ref "RN13") (pin "7") (pinfunction "7_7") (pintype "input"))
    )
    (net (code "50") (name "Net-(LED7-G)") (class "Default")
      (node (ref "LED7") (pin "1") (pinfunction "G_1") (pintype "unspecified"))
      (node (ref "RN13") (pin "6") (pinfunction "6_6") (pintype "input"))
    )
    (net (code "51") (name "Net-(RN2-Pad1)") (class "Default")
      (node (ref "RN2") (pin "1") (pinfunction "1_1") (pintype "input"))
      (node (ref "U4") (pin "13") (pinfunction "A_13") (pintype "unspecified"))
    )
    (net (code "52") (name "Net-(RN2-Pad2)") (class "Default")
      (node (ref "RN2") (pin "2") (pinfunction "2_2") (pintype "input"))
      (node (ref "U4") (pin "12") (pinfunction "B_12") (pintype "unspecified"))
    )
    (net (code "53") (name "Net-(RN2-Pad3)") (class "Default")
      (node (ref "RN2") (pin "3") (pinfunction "3_3") (pintype "input"))
      (node (ref "U4") (pin "11") (pinfunction "C_11") (pintype "unspecified"))
    )
    (net (code "54") (name "Net-(RN2-Pad4)") (class "Default")
      (node (ref "RN2") (pin "4") (pinfunction "4_4") (pintype "input"))
      (node (ref "U4") (pin "10") (pinfunction "D_10") (pintype "unspecified"))
    )
    (net (code "55") (name "Net-(RN4-Pad1)") (class "Default")
      (node (ref "RN4") (pin "1") (pinfunction "1_1") (pintype "input"))
      (node (ref "U6") (pin "13") (pinfunction "A_13") (pintype "unspecified"))
    )
    (net (code "56") (name "Net-(RN4-Pad2)") (class "Default")
      (node (ref "RN4") (pin "2") (pinfunction "2_2") (pintype "input"))
      (node (ref "U6") (pin "12") (pinfunction "B_12") (pintype "unspecified"))
    )
    (net (code "57") (name "Net-(RN4-Pad3)") (class "Default")
      (node (ref "RN4") (pin "3") (pinfunction "3_3") (pintype "input"))
      (node (ref "U6") (pin "11") (pinfunction "C_11") (pintype "unspecified"))
    )
    (net (code "58") (name "Net-(RN4-Pad4)") (class "Default")
      (node (ref "RN4") (pin "4") (pinfunction "4_4") (pintype "input"))
      (node (ref "U6") (pin "10") (pinfunction "D_10") (pintype "unspecified"))
    )
    (net (code "59") (name "Net-(RN6-Pad1)") (class "Default")
      (node (ref "RN6") (pin "1") (pinfunction "1_1") (pintype "input"))
      (node (ref "U10") (pin "13") (pinfunction "A_13") (pintype "unspecified"))
    )
    (net (code "60") (name "Net-(RN6-Pad2)") (class "Default")
      (node (ref "RN6") (pin "2") (pinfunction "2_2") (pintype "input"))
      (node (ref "U10") (pin "12") (pinfunction "B_12") (pintype "unspecified"))
    )
    (net (code "61") (name "Net-(RN6-Pad3)") (class "Default")
      (node (ref "RN6") (pin "3") (pinfunction "3_3") (pintype "input"))
      (node (ref "U10") (pin "11") (pinfunction "C_11") (pintype "unspecified"))
    )
    (net (code "62") (name "Net-(RN6-Pad4)") (class "Default")
      (node (ref "RN6") (pin "4") (pinfunction "4_4") (pintype "input"))
      (node (ref "U10") (pin "10") (pinfunction "D_10") (pintype "unspecified"))
    )
    (net (code "63") (name "Net-(RN8-Pad1)") (class "Default")
      (node (ref "RN8") (pin "1") (pinfunction "1_1") (pintype "input"))
      (node (ref "U12") (pin "13") (pinfunction "A_13") (pintype "unspecified"))
    )
    (net (code "64") (name "Net-(RN8-Pad2)") (class "Default")
      (node (ref "RN8") (pin "2") (pinfunction "2_2") (pintype "input"))
      (node (ref "U12") (pin "12") (pinfunction "B_12") (pintype "unspecified"))
    )
    (net (code "65") (name "Net-(RN8-Pad3)") (class "Default")
      (node (ref "RN8") (pin "3") (pinfunction "3_3") (pintype "input"))
      (node (ref "U12") (pin "11") (pinfunction "C_11") (pintype "unspecified"))
    )
    (net (code "66") (name "Net-(RN8-Pad4)") (class "Default")
      (node (ref "RN8") (pin "4") (pinfunction "4_4") (pintype "input"))
      (node (ref "U12") (pin "10") (pinfunction "D_10") (pintype "unspecified"))
    )
    (net (code "67") (name "Net-(RN10-Pad1)") (class "Default")
      (node (ref "RN10") (pin "1") (pinfunction "1_1") (pintype "input"))
      (node (ref "U15") (pin "13") (pinfunction "A_13") (pintype "unspecified"))
    )
    (net (code "68") (name "Net-(RN10-Pad2)") (class "Default")
      (node (ref "RN10") (pin "2") (pinfunction "2_2") (pintype "input"))
      (node (ref "U15") (pin "12") (pinfunction "B_12") (pintype "unspecified"))
    )
    (net (code "69") (name "Net-(RN10-Pad3)") (class "Default")
      (node (ref "RN10") (pin "3") (pinfunction "3_3") (pintype "input"))
      (node (ref "U15") (pin "11") (pinfunction "C_11") (pintype "unspecified"))
    )
    (net (code "70") (name "Net-(RN10-Pad4)") (class "Default")
      (node (ref "RN10") (pin "4") (pinfunction "4_4") (pintype "input"))
      (node (ref "U15") (pin "10") (pinfunction "D_10") (pintype "unspecified"))
    )
    (net (code "71") (name "Net-(RN12-Pad1)") (class "Default")
      (node (ref "RN12") (pin "1") (pinfunction "1_1") (pintype "input"))
      (node (ref "U17") (pin "13") (pinfunction "A_13") (pintype "unspecified"))
    )
    (net (code "72") (name "Net-(RN12-Pad2)") (class "Default")
      (node (ref "RN12") (pin "2") (pinfunction "2_2") (pintype "input"))
      (node (ref "U17") (pin "12") (pinfunction "B_12") (pintype "unspecified"))
    )
    (net (code "73") (name "Net-(RN12-Pad3)") (class "Default")
      (node (ref "RN12") (pin "3") (pinfunction "3_3") (pintype "input"))
      (node (ref "U17") (pin "11") (pinfunction "C_11") (pintype "unspecified"))
    )
    (net (code "74") (name "Net-(RN12-Pad4)") (class "Default")
      (node (ref "RN12") (pin "4") (pinfunction "4_4") (pintype "input"))
      (node (ref "U17") (pin "10") (pinfunction "D_10") (pintype "unspecified"))
    )
    (net (code "75") (name "Net-(SW1-Pad2)") (class "Default")
      (node (ref "SW1") (pin "2") (pinfunction "2_2") (pintype "unspecified"))
      (node (ref "U3") (pin "1") (pinfunction "1_1") (pintype "unspecified"))
    )
    (net (code "76") (name "Net-(SW2-Pad2)") (class "Default")
      (node (ref "SW2") (pin "2") (pinfunction "2_2") (pintype "unspecified"))
      (node (ref "U9") (pin "1") (pinfunction "1_1") (pintype "unspecified"))
    )
    (net (code "77") (name "Net-(SW3-Pad2)") (class "Default")
      (node (ref "SW3") (pin "2") (pinfunction "2_2") (pintype "unspecified"))
      (node (ref "U14") (pin "1") (pinfunction "1_1") (pintype "unspecified"))
    )
    (net (code "78") (name "Net-(U1-CP)") (class "Default")
      (node (ref "U1") (pin "2") (pinfunction "CP_2") (pintype "unspecified"))
      (node (ref "U5") (pin "15") (pinfunction "TC_15") (pintype "unspecified"))
    )
    (net (code "79") (name "Net-(U1-MR#)") (class "Default")
      (node (ref "U1") (pin "1") (pinfunction "MR#_1") (pintype "unspecified"))
      (node (ref "U18") (pin "8") (pinfunction "3Y_8") (pintype "unspecified"))
      (node (ref "U19") (pin "13") (pinfunction "6A_13") (pintype "unspecified"))
    )
    (net (code "80") (name "Net-(U1-Q0)") (class "Default")
      (node (ref "U1") (pin "14") (pinfunction "Q0_14") (pintype "unspecified"))
      (node (ref "U4") (pin "7") (pinfunction "A_7") (pintype "unspecified"))
    )
    (net (code "81") (name "Net-(U1-Q1)") (class "Default")
      (node (ref "U1") (pin "13") (pinfunction "Q1_13") (pintype "unspecified"))
      (node (ref "U18") (pin "10") (pinfunction "3A_10") (pintype "unspecified"))
      (node (ref "U4") (pin "1") (pinfunction "B_1") (pintype "unspecified"))
    )
    (net (code "82") (name "Net-(U1-Q2)") (class "Default")
      (node (ref "U1") (pin "12") (pinfunction "Q2_12") (pintype "unspecified"))
      (node (ref "U18") (pin "9") (pinfunction "3B_9") (pintype "unspecified"))
      (node (ref "U4") (pin "2") (pinfunction "C_2") (pintype "unspecified"))
    )
    (net (code "83") (name "Net-(U1-Q3)") (class "Default")
      (node (ref "U1") (pin "11") (pinfunction "Q3_11") (pintype "unspecified"))
      (node (ref "U4") (pin "6") (pinfunction "D_6") (pintype "unspecified"))
    )
    (net (code "84") (name "Net-(U4-E)") (class "Default")
      (node (ref "RN3") (pin "1") (pinfunction "1_1") (pintype "input"))
      (node (ref "U4") (pin "9") (pinfunction "E_9") (pintype "unspecified"))
    )
    (net (code "85") (name "Net-(U4-F)") (class "Default")
      (node (ref "RN3") (pin "2") (pinfunction "2_2") (pintype "input"))
      (node (ref "U4") (pin "15") (pinfunction "F_15") (pintype "unspecified"))
    )
    (net (code "86") (name "Net-(U4-G)") (class "Default")
      (node (ref "RN3") (pin "3") (pinfunction "3_3") (pintype "input"))
      (node (ref "U4") (pin "14") (pinfunction "G_14") (pintype "unspecified"))
    )
    (net (code "87") (name "Net-(U5-CP)") (class "Default")
      (node (ref "U3") (pin "2") (pinfunction "2_2") (pintype "unspecified"))
      (node (ref "U5") (pin "2") (pinfunction "CP_2") (pintype "unspecified"))
    )
    (net (code "88") (name "Net-(U5-Q0)") (class "Default")
      (node (ref "U5") (pin "14") (pinfunction "Q0_14") (pintype "unspecified"))
      (node (ref "U6") (pin "7") (pinfunction "A_7") (pintype "unspecified"))
    )
    (net (code "89") (name "Net-(U5-Q1)") (class "Default")
      (node (ref "U5") (pin "13") (pinfunction "Q1_13") (pintype "unspecified"))
      (node (ref "U6") (pin "1") (pinfunction "B_1") (pintype "unspecified"))
    )
    (net (code "90") (name "Net-(U5-Q2)") (class "Default")
      (node (ref "U5") (pin "12") (pinfunction "Q2_12") (pintype "unspecified"))
      (node (ref "U6") (pin "2") (pinfunction "C_2") (pintype "unspecified"))
    )
    (net (code "91") (name "Net-(U5-Q3)") (class "Default")
      (node (ref "U5") (pin "11") (pinfunction "Q3_11") (pintype "unspecified"))
      (node (ref "U6") (pin "6") (pinfunction "D_6") (pintype "unspecified"))
    )
    (net (code "92") (name "Net-(U6-E)") (class "Default")
      (node (ref "RN5") (pin "1") (pinfunction "1_1") (pintype "input"))
      (node (ref "U6") (pin "9") (pinfunction "E_9") (pintype "unspecified"))
    )
    (net (code "93") (name "Net-(U6-F)") (class "Default")
      (node (ref "RN5") (pin "2") (pinfunction "2_2") (pintype "input"))
      (node (ref "U6") (pin "15") (pinfunction "F_15") (pintype "unspecified"))
    )
    (net (code "94") (name "Net-(U6-G)") (class "Default")
      (node (ref "RN5") (pin "3") (pinfunction "3_3") (pintype "input"))
      (node (ref "U6") (pin "14") (pinfunction "G_14") (pintype "unspecified"))
    )
    (net (code "95") (name "Net-(U7-CONT)") (class "Default")
      (node (ref "C2") (pin "2") (pinfunction "2_2") (pintype "unspecified"))
      (node (ref "U7") (pin "5") (pinfunction "CONT_5") (pintype "unspecified"))
    )
    (net (code "96") (name "Net-(U7-DISCH)") (class "Default")
      (node (ref "R1") (pin "1") (pinfunction "1_1") (pintype "unspecified"))
      (node (ref "R2") (pin "1") (pinfunction "1_1") (pintype "unspecified"))
      (node (ref "U7") (pin "7") (pinfunction "DISCH_7") (pintype "unspecified"))
    )
    (net (code "97") (name "Net-(U7-OUT)") (class "Default")
      (node (ref "U3") (pin "3") (pinfunction "3_3") (pintype "unspecified"))
      (node (ref "U7") (pin "3") (pinfunction "OUT_3") (pintype "unspecified"))
    )
    (net (code "98") (name "Net-(U7-THRES)") (class "Default")
      (node (ref "C1") (pin "1") (pinfunction "1_1") (pintype "unspecified"))
      (node (ref "R1") (pin "2") (pinfunction "2_2") (pintype "unspecified"))
      (node (ref "U7") (pin "2") (pinfunction "TRIG_2") (pintype "unspecified"))
      (node (ref "U7") (pin "6") (pinfunction "THRES_6") (pintype "unspecified"))
    )
    (net (code "99") (name "Net-(U8-Q0)") (class "Default")
      (node (ref "U10") (pin "7") (pinfunction "A_7") (pintype "unspecified"))
      (node (ref "U8") (pin "14") (pinfunction "Q0_14") (pintype "unspecified"))
    )
    (net (code "100") (name "Net-(U8-Q3)") (class "Default")
      (node (ref "U10") (pin "6") (pinfunction "D_6") (pintype "unspecified"))
      (node (ref "U8") (pin "11") (pinfunction "Q3_11") (pintype "unspecified"))
    )
    (net (code "101") (name "Net-(U10-E)") (class "Default")
      (node (ref "RN7") (pin "1") (pinfunction "1_1") (pintype "input"))
      (node (ref "U10") (pin "9") (pinfunction "E_9") (pintype "unspecified"))
    )
    (net (code "102") (name "Net-(U10-F)") (class "Default")
      (node (ref "RN7") (pin "2") (pinfunction "2_2") (pintype "input"))
      (node (ref "U10") (pin "15") (pinfunction "F_15") (pintype "unspecified"))
    )
    (net (code "103") (name "Net-(U10-G)") (class "Default")
      (node (ref "RN7") (pin "3") (pinfunction "3_3") (pintype "input"))
      (node (ref "U10") (pin "14") (pinfunction "G_14") (pintype "unspecified"))
    )
    (net (code "104") (name "Net-(U11-CP)") (class "Default")
      (node (ref "U11") (pin "2") (pinfunction "CP_2") (pintype "unspecified"))
      (node (ref "U9") (pin "2") (pinfunction "2_2") (pintype "unspecified"))
    )
    (net (code "105") (name "Net-(U11-Q0)") (class "Default")
      (node (ref "U11") (pin "14") (pinfunction "Q0_14") (pintype "unspecified"))
      (node (ref "U12") (pin "7") (pinfunction "A_7") (pintype "unspecified"))
    )
    (net (code "106") (name "Net-(U11-Q1)") (class "Default")
      (node (ref "U11") (pin "13") (pinfunction "Q1_13") (pintype "unspecified"))
      (node (ref "U12") (pin "1") (pinfunction "B_1") (pintype "unspecified"))
    )
    (net (code "107") (name "Net-(U11-Q2)") (class "Default")
      (node (ref "U11") (pin "12") (pinfunction "Q2_12") (pintype "unspecified"))
      (node (ref "U12") (pin "2") (pinfunction "C_2") (pintype "unspecified"))
    )
    (net (code "108") (name "Net-(U11-Q3)") (class "Default")
      (node (ref "U11") (pin "11") (pinfunction "Q3_11") (pintype "unspecified"))
      (node (ref "U12") (pin "6") (pinfunction "D_6") (pintype "unspecified"))
    )
    (net (code "109") (name "Net-(U11-TC)") (class "Default")
      (node (ref "U11") (pin "15") (pinfunction "TC_15") (pintype "unspecified"))
      (node (ref "U8") (pin "2") (pinfunction "CP_2") (pintype "unspecified"))
    )
    (net (code "110") (name "Net-(U12-E)") (class "Default")
      (node (ref "RN9") (pin "1") (pinfunction "1_1") (pintype "input"))
      (node (ref "U12") (pin "9") (pinfunction "E_9") (pintype "unspecified"))
    )
    (net (code "111") (name "Net-(U12-F)") (class "Default")
      (node (ref "RN9") (pin "2") (pinfunction "2_2") (pintype "input"))
      (node (ref "U12") (pin "15") (pinfunction "F_15") (pintype "unspecified"))
    )
    (net (code "112") (name "Net-(U12-G)") (class "Default")
      (node (ref "RN9") (pin "3") (pinfunction "3_3") (pintype "input"))
      (node (ref "U12") (pin "14") (pinfunction "G_14") (pintype "unspecified"))
    )
    (net (code "113") (name "Net-(U13-CP)") (class "Default")
      (node (ref "U13") (pin "2") (pinfunction "CP_2") (pintype "unspecified"))
      (node (ref "U16") (pin "15") (pinfunction "TC_15") (pintype "unspecified"))
    )
    (net (code "114") (name "Net-(U13-MR#)") (class "Default")
      (node (ref "U13") (pin "1") (pinfunction "MR#_1") (pintype "unspecified"))
      (node (ref "U18") (pin "6") (pinfunction "2Y_6") (pintype "unspecified"))
    )
    (net (code "115") (name "Net-(U13-Q0)") (class "Default")
      (node (ref "U13") (pin "14") (pinfunction "Q0_14") (pintype "unspecified"))
      (node (ref "U15") (pin "7") (pinfunction "A_7") (pintype "unspecified"))
    )
    (net (code "116") (name "Net-(U13-Q1)") (class "Default")
      (node (ref "U13") (pin "13") (pinfunction "Q1_13") (pintype "unspecified"))
      (node (ref "U15") (pin "1") (pinfunction "B_1") (pintype "unspecified"))
      (node (ref "U18") (pin "4") (pinfunction "2A_4") (pintype "unspecified"))
    )
    (net (code "117") (name "Net-(U13-Q2)") (class "Default")
      (node (ref "U13") (pin "12") (pinfunction "Q2_12") (pintype "unspecified"))
      (node (ref "U15") (pin "2") (pinfunction "C_2") (pintype "unspecified"))
    )
    (net (code "118") (name "Net-(U13-Q3)") (class "Default")
      (node (ref "U13") (pin "11") (pinfunction "Q3_11") (pintype "unspecified"))
      (node (ref "U15") (pin "6") (pinfunction "D_6") (pintype "unspecified"))
    )
    (net (code "119") (name "Net-(U15-E)") (class "Default")
      (node (ref "RN11") (pin "1") (pinfunction "1_1") (pintype "input"))
      (node (ref "U15") (pin "9") (pinfunction "E_9") (pintype "unspecified"))
    )
    (net (code "120") (name "Net-(U15-F)") (class "Default")
      (node (ref "RN11") (pin "2") (pinfunction "2_2") (pintype "input"))
      (node (ref "U15") (pin "15") (pinfunction "F_15") (pintype "unspecified"))
    )
    (net (code "121") (name "Net-(U15-G)") (class "Default")
      (node (ref "RN11") (pin "3") (pinfunction "3_3") (pintype "input"))
      (node (ref "U15") (pin "14") (pinfunction "G_14") (pintype "unspecified"))
    )
    (net (code "122") (name "Net-(U16-CP)") (class "Default")
      (node (ref "U14") (pin "2") (pinfunction "2_2") (pintype "unspecified"))
      (node (ref "U16") (pin "2") (pinfunction "CP_2") (pintype "unspecified"))
    )
    (net (code "123") (name "Net-(U16-Q0)") (class "Default")
      (node (ref "U16") (pin "14") (pinfunction "Q0_14") (pintype "unspecified"))
      (node (ref "U17") (pin "7") (pinfunction "A_7") (pintype "unspecified"))
    )
    (net (code "124") (name "Net-(U16-Q1)") (class "Default")
      (node (ref "U16") (pin "13") (pinfunction "Q1_13") (pintype "unspecified"))
      (node (ref "U17") (pin "1") (pinfunction "B_1") (pintype "unspecified"))
    )
    (net (code "125") (name "Net-(U16-Q2)") (class "Default")
      (node (ref "U16") (pin "12") (pinfunction "Q2_12") (pintype "unspecified"))
      (node (ref "U17") (pin "2") (pinfunction "C_2") (pintype "unspecified"))
      (node (ref "U18") (pin "5") (pinfunction "2B_5") (pintype "unspecified"))
    )
    (net (code "126") (name "Net-(U16-Q3)") (class "Default")
      (node (ref "U16") (pin "11") (pinfunction "Q3_11") (pintype "unspecified"))
      (node (ref "U17") (pin "6") (pinfunction "D_6") (pintype "unspecified"))
    )
    (net (code "127") (name "Net-(U17-E)") (class "Default")
      (node (ref "RN13") (pin "1") (pinfunction "1_1") (pintype "input"))
      (node (ref "U17") (pin "9") (pinfunction "E_9") (pintype "unspecified"))
    )
    (net (code "128") (name "Net-(U17-F)") (class "Default")
      (node (ref "RN13") (pin "2") (pinfunction "2_2") (pintype "input"))
      (node (ref "U17") (pin "15") (pinfunction "F_15") (pintype "unspecified"))
    )
    (net (code "129") (name "Net-(U17-G)") (class "Default")
      (node (ref "RN13") (pin "3") (pinfunction "3_3") (pintype "input"))
      (node (ref "U17") (pin "14") (pinfunction "G_14") (pintype "unspecified"))
    )
    (net (code "130") (name "Net-(U18-4A)") (class "Default")
      (node (ref "U10") (pin "2") (pinfunction "C_2") (pintype "unspecified"))
      (node (ref "U18") (pin "13") (pinfunction "4A_13") (pintype "unspecified"))
      (node (ref "U8") (pin "12") (pinfunction "Q2_12") (pintype "unspecified"))
    )
    (net (code "131") (name "Net-(U18-4B)") (class "Default")
      (node (ref "U10") (pin "1") (pinfunction "B_1") (pintype "unspecified"))
      (node (ref "U18") (pin "12") (pinfunction "4B_12") (pintype "unspecified"))
      (node (ref "U8") (pin "13") (pinfunction "Q1_13") (pintype "unspecified"))
    )
    (net (code "132") (name "Net-(U18-4Y)") (class "Default")
      (node (ref "U18") (pin "11") (pinfunction "4Y_11") (pintype "unspecified"))
      (node (ref "U19") (pin "11") (pinfunction "5A_11") (pintype "unspecified"))
      (node (ref "U8") (pin "1") (pinfunction "MR#_1") (pintype "unspecified"))
    )
    (net (code "133") (name "Net-(U19-5Y)") (class "Default")
      (node (ref "U14") (pin "3") (pinfunction "3_3") (pintype "unspecified"))
      (node (ref "U19") (pin "10") (pinfunction "5Y_10") (pintype "unspecified"))
    )
    (net (code "134") (name "Net-(U19-6Y)") (class "Default")
      (node (ref "U19") (pin "12") (pinfunction "6Y_12") (pintype "unspecified"))
      (node (ref "U9") (pin "3") (pinfunction "3_3") (pintype "unspecified"))
    )
    (net (code "135") (name "unconnected-(U1-TC-Pad15)") (class "Default")
      (node (ref "U1") (pin "15") (pinfunction "TC_15") (pintype "unspecified"))
    )
    (net (code "136") (name "unconnected-(U4-BI#{slash}RBO#-Pad4)") (class "Default")
      (node (ref "U4") (pin "4") (pinfunction "BI#/RBO#_4") (pintype "unspecified"))
    )
    (net (code "137") (name "unconnected-(U4-LT#-Pad3)") (class "Default")
      (node (ref "U4") (pin "3") (pinfunction "LT#_3") (pintype "unspecified"))
    )
    (net (code "138") (name "unconnected-(U4-RBI#-Pad5)") (class "Default")
      (node (ref "U4") (pin "5") (pinfunction "RBI#_5") (pintype "unspecified"))
    )
    (net (code "139") (name "unconnected-(U6-BI#{slash}RBO#-Pad4)") (class "Default")
      (node (ref "U6") (pin "4") (pinfunction "BI#/RBO#_4") (pintype "unspecified"))
    )
    (net (code "140") (name "unconnected-(U6-LT#-Pad3)") (class "Default")
      (node (ref "U6") (pin "3") (pinfunction "LT#_3") (pintype "unspecified"))
    )
    (net (code "141") (name "unconnected-(U6-RBI#-Pad5)") (class "Default")
      (node (ref "U6") (pin "5") (pinfunction "RBI#_5") (pintype "unspecified"))
    )
    (net (code "142") (name "unconnected-(U8-TC-Pad15)") (class "Default")
      (node (ref "U8") (pin "15") (pinfunction "TC_15") (pintype "unspecified"))
    )
    (net (code "143") (name "unconnected-(U10-BI#{slash}RBO#-Pad4)") (class "Default")
      (node (ref "U10") (pin "4") (pinfunction "BI#/RBO#_4") (pintype "unspecified"))
    )
    (net (code "144") (name "unconnected-(U10-LT#-Pad3)") (class "Default")
      (node (ref "U10") (pin "3") (pinfunction "LT#_3") (pintype "unspecified"))
    )
    (net (code "145") (name "unconnected-(U10-RBI#-Pad5)") (class "Default")
      (node (ref "U10") (pin "5") (pinfunction "RBI#_5") (pintype "unspecified"))
    )
    (net (code "146") (name "unconnected-(U12-BI#{slash}RBO#-Pad4)") (class "Default")
      (node (ref "U12") (pin "4") (pinfunction "BI#/RBO#_4") (pintype "unspecified"))
    )
    (net (code "147") (name "unconnected-(U12-LT#-Pad3)") (class "Default")
      (node (ref "U12") (pin "3") (pinfunction "LT#_3") (pintype "unspecified"))
    )
    (net (code "148") (name "unconnected-(U12-RBI#-Pad5)") (class "Default")
      (node (ref "U12") (pin "5") (pinfunction "RBI#_5") (pintype "unspecified"))
    )
    (net (code "149") (name "unconnected-(U13-TC-Pad15)") (class "Default")
      (node (ref "U13") (pin "15") (pinfunction "TC_15") (pintype "unspecified"))
    )
    (net (code "150") (name "unconnected-(U15-BI#{slash}RBO#-Pad4)") (class "Default")
      (node (ref "U15") (pin "4") (pinfunction "BI#/RBO#_4") (pintype "unspecified"))
    )
    (net (code "151") (name "unconnected-(U15-LT#-Pad3)") (class "Default")
      (node (ref "U15") (pin "3") (pinfunction "LT#_3") (pintype "unspecified"))
    )
    (net (code "152") (name "unconnected-(U15-RBI#-Pad5)") (class "Default")
      (node (ref "U15") (pin "5") (pinfunction "RBI#_5") (pintype "unspecified"))
    )
    (net (code "153") (name "unconnected-(U17-BI#{slash}RBO#-Pad4)") (class "Default")
      (node (ref "U17") (pin "4") (pinfunction "BI#/RBO#_4") (pintype "unspecified"))
    )
    (net (code "154") (name "unconnected-(U17-LT#-Pad3)") (class "Default")
      (node (ref "U17") (pin "3") (pinfunction "LT#_3") (pintype "unspecified"))
    )
    (net (code "155") (name "unconnected-(U17-RBI#-Pad5)") (class "Default")
      (node (ref "U17") (pin "5") (pinfunction "RBI#_5") (pintype "unspecified"))
    )
    (net (code "156") (name "unconnected-(U18-1A-Pad1)") (class "Default")
      (node (ref "U18") (pin "1") (pinfunction "1A_1") (pintype "unspecified"))
    )
    (net (code "157") (name "unconnected-(U18-1B-Pad2)") (class "Default")
      (node (ref "U18") (pin "2") (pinfunction "1B_2") (pintype "unspecified"))
    )
    (net (code "158") (name "unconnected-(U18-1Y-Pad3)") (class "Default")
      (node (ref "U18") (pin "3") (pinfunction "1Y_3") (pintype "unspecified"))
    )
    (net (code "159") (name "unconnected-(U19-1A-Pad1)") (class "Default")
      (node (ref "U19") (pin "1") (pinfunction "1A_1") (pintype "unspecified"))
    )
    (net (code "160") (name "unconnected-(U19-1Y-Pad2)") (class "Default")
      (node (ref "U19") (pin "2") (pinfunction "1Y_2") (pintype "unspecified"))
    )
    (net (code "161") (name "unconnected-(U19-2A-Pad3)") (class "Default")
      (node (ref "U19") (pin "3") (pinfunction "2A_3") (pintype "unspecified"))
    )
    (net (code "162") (name "unconnected-(U19-2Y-Pad4)") (class "Default")
      (node (ref "U19") (pin "4") (pinfunction "2Y_4") (pintype "unspecified"))
    )
    (net (code "163") (name "unconnected-(U19-3A-Pad5)") (class "Default")
      (node (ref "U19") (pin "5") (pinfunction "3A_5") (pintype "unspecified"))
    )
    (net (code "164") (name "unconnected-(U19-3Y-Pad6)") (class "Default")
      (node (ref "U19") (pin "6") (pinfunction "3Y_6") (pintype "unspecified"))
    )
    (net (code "165") (name "unconnected-(U19-4A-Pad9)") (class "Default")
      (node (ref "U19") (pin "9") (pinfunction "4A_9") (pintype "unspecified"))
    )
    (net (code "166") (name "unconnected-(U19-4Y-Pad8)") (class "Default")
      (node (ref "U19") (pin "8") (pinfunction "4Y_8") (pintype "unspecified"))
    )
  )
)
